# low_voltage_detection_circuit.net
KiCad netlist of a schematic drawn in EAGLE
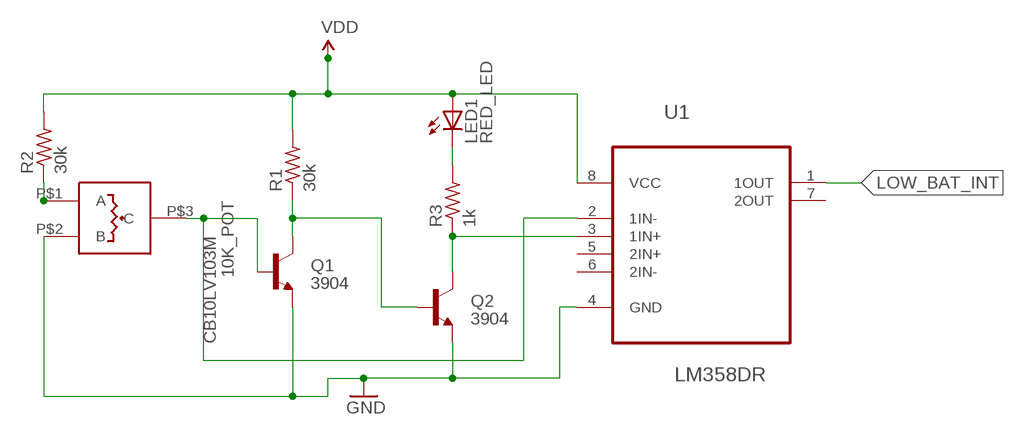
[diagram p0: schematic, sheet 1]

(export (version "E")
  (design (tool "Eeschema 10.0.6"))
  (components
    (comp (ref "10K_POT")
      (value "CB10LV103M")
      (footprint "eagle-import:CB10")
      (libsource (lib "eagle-import") (part "CB10LV103M"))
    )
    (comp (ref "LED1")
      (value "RED_LED")
      (footprint "eagle-import:LED3MM")
      (libsource (lib "eagle-import") (part "LED3MM"))
    )
    (comp (ref "Q1")
      (value "3904")
      (footprint "eagle-import:SOT-23")
      (libsource (lib "eagle-import") (part "TRANSISTOR_NPNMMBT3904"))
    )
    (comp (ref "Q2")
      (value "3904")
      (footprint "eagle-import:SOT-23")
      (libsource (lib "eagle-import") (part "TRANSISTOR_NPNMMBT3904"))
    )
    (comp (ref "R1")
      (value "30k")
      (footprint "eagle-import:R1206")
      (libsource (lib "eagle-import") (part "R-US_R1206"))
    )
    (comp (ref "R2")
      (value "30k")
      (footprint "eagle-import:R1206")
      (libsource (lib "eagle-import") (part "R-US_R1206"))
    )
    (comp (ref "R3")
      (value "1k")
      (footprint "eagle-import:R1206")
      (libsource (lib "eagle-import") (part "R-US_R1206"))
    )
    (comp (ref "U1")
      (value "LM358DR")
      (footprint "eagle-import:SOIC127P600X175-8N")
      (libsource (lib "eagle-import") (part "LM358DR"))
    )
  )
  (nets
    (net (code "1") (name "GND") (class "Default")
      (node (ref "10K_POT") (pin "P$2") (pinfunction "B_P$2") (pintype "bidirectional"))
      (node (ref "Q1") (pin "2") (pinfunction "E_2") (pintype "passive"))
      (node (ref "Q2") (pin "2") (pinfunction "E_2") (pintype "passive"))
      (node (ref "U1") (pin "4") (pinfunction "GND_4") (pintype "passive"))
    )
    (net (code "2") (name "LOW_BAT_INT") (class "Default")
      (node (ref "U1") (pin "1") (pinfunction "1OUT_1") (pintype "output"))
    )
    (net (code "3") (name "Net-(10K_POT-A)") (class "Default")
      (node (ref "10K_POT") (pin "P$1") (pinfunction "A_P$1") (pintype "bidirectional"))
      (node (ref "R2") (pin "1") (pinfunction "1_1") (pintype "passive"))
    )
    (net (code "4") (name "Net-(10K_POT-C)") (class "Default")
      (node (ref "10K_POT") (pin "P$3") (pinfunction "C_P$3") (pintype "bidirectional"))
      (node (ref "Q1") (pin "1") (pinfunction "B_1") (pintype "passive"))
      (node (ref "U1") (pin "2") (pinfunction "1IN-_2") (pintype "input"))
    )
    (net (code "5") (name "Net-(LED1-C)") (class "Default")
      (node (ref "LED1") (pin "K") (pinfunction "C_K") (pintype "passive"))
      (node (ref "R3") (pin "2") (pinfunction "2_2") (pintype "passive"))
    )
    (net (code "6") (name "Net-(Q1-C)") (class "Default")
      (node (ref "Q1") (pin "3") (pinfunction "C_3") (pintype "passive"))
      (node (ref "Q2") (pin "1") (pinfunction "B_1") (pintype "passive"))
      (node (ref "R1") (pin "1") (pinfunction "1_1") (pintype "passive"))
    )
    (net (code "7") (name "Net-(Q2-C)") (class "Default")
      (node (ref "Q2") (pin "3") (pinfunction "C_3") (pintype "passive"))
      (node (ref "R3") (pin "1") (pinfunction "1_1") (pintype "passive"))
      (node (ref "U1") (pin "3") (pinfunction "1IN+_3") (pintype "input"))
    )
    (net (code "8") (name "VDD") (class "Default")
      (node (ref "LED1") (pin "A") (pinfunction "A_A") (pintype "passive"))
      (node (ref "R1") (pin "2") (pinfunction "2_2") (pintype "passive"))
      (node (ref "R2") (pin "2") (pinfunction "2_2") (pintype "passive"))
      (node (ref "U1") (pin "8") (pinfunction "VCC_8") (pintype "power_in"))
    )
    (net (code "9") (name "unconnected-(U1-2IN+-Pad5)") (class "Default")
      (node (ref "U1") (pin "5") (pinfunction "2IN+_5") (pintype "input"))
    )
    (net (code "10") (name "unconnected-(U1-2IN--Pad6)") (class "Default")
      (node (ref "U1") (pin "6") (pinfunction "2IN-_6") (pintype "input"))
    )
    (net (code "11") (name "unconnected-(U1-2OUT-Pad7)") (class "Default")
      (node (ref "U1") (pin "7") (pinfunction "2OUT_7") (pintype "output"))
    )
  )
)
